# SCH_Amogus-Buzzer_2024-08-13.net
KiCad netlist of a schematic drawn in EasyEDA
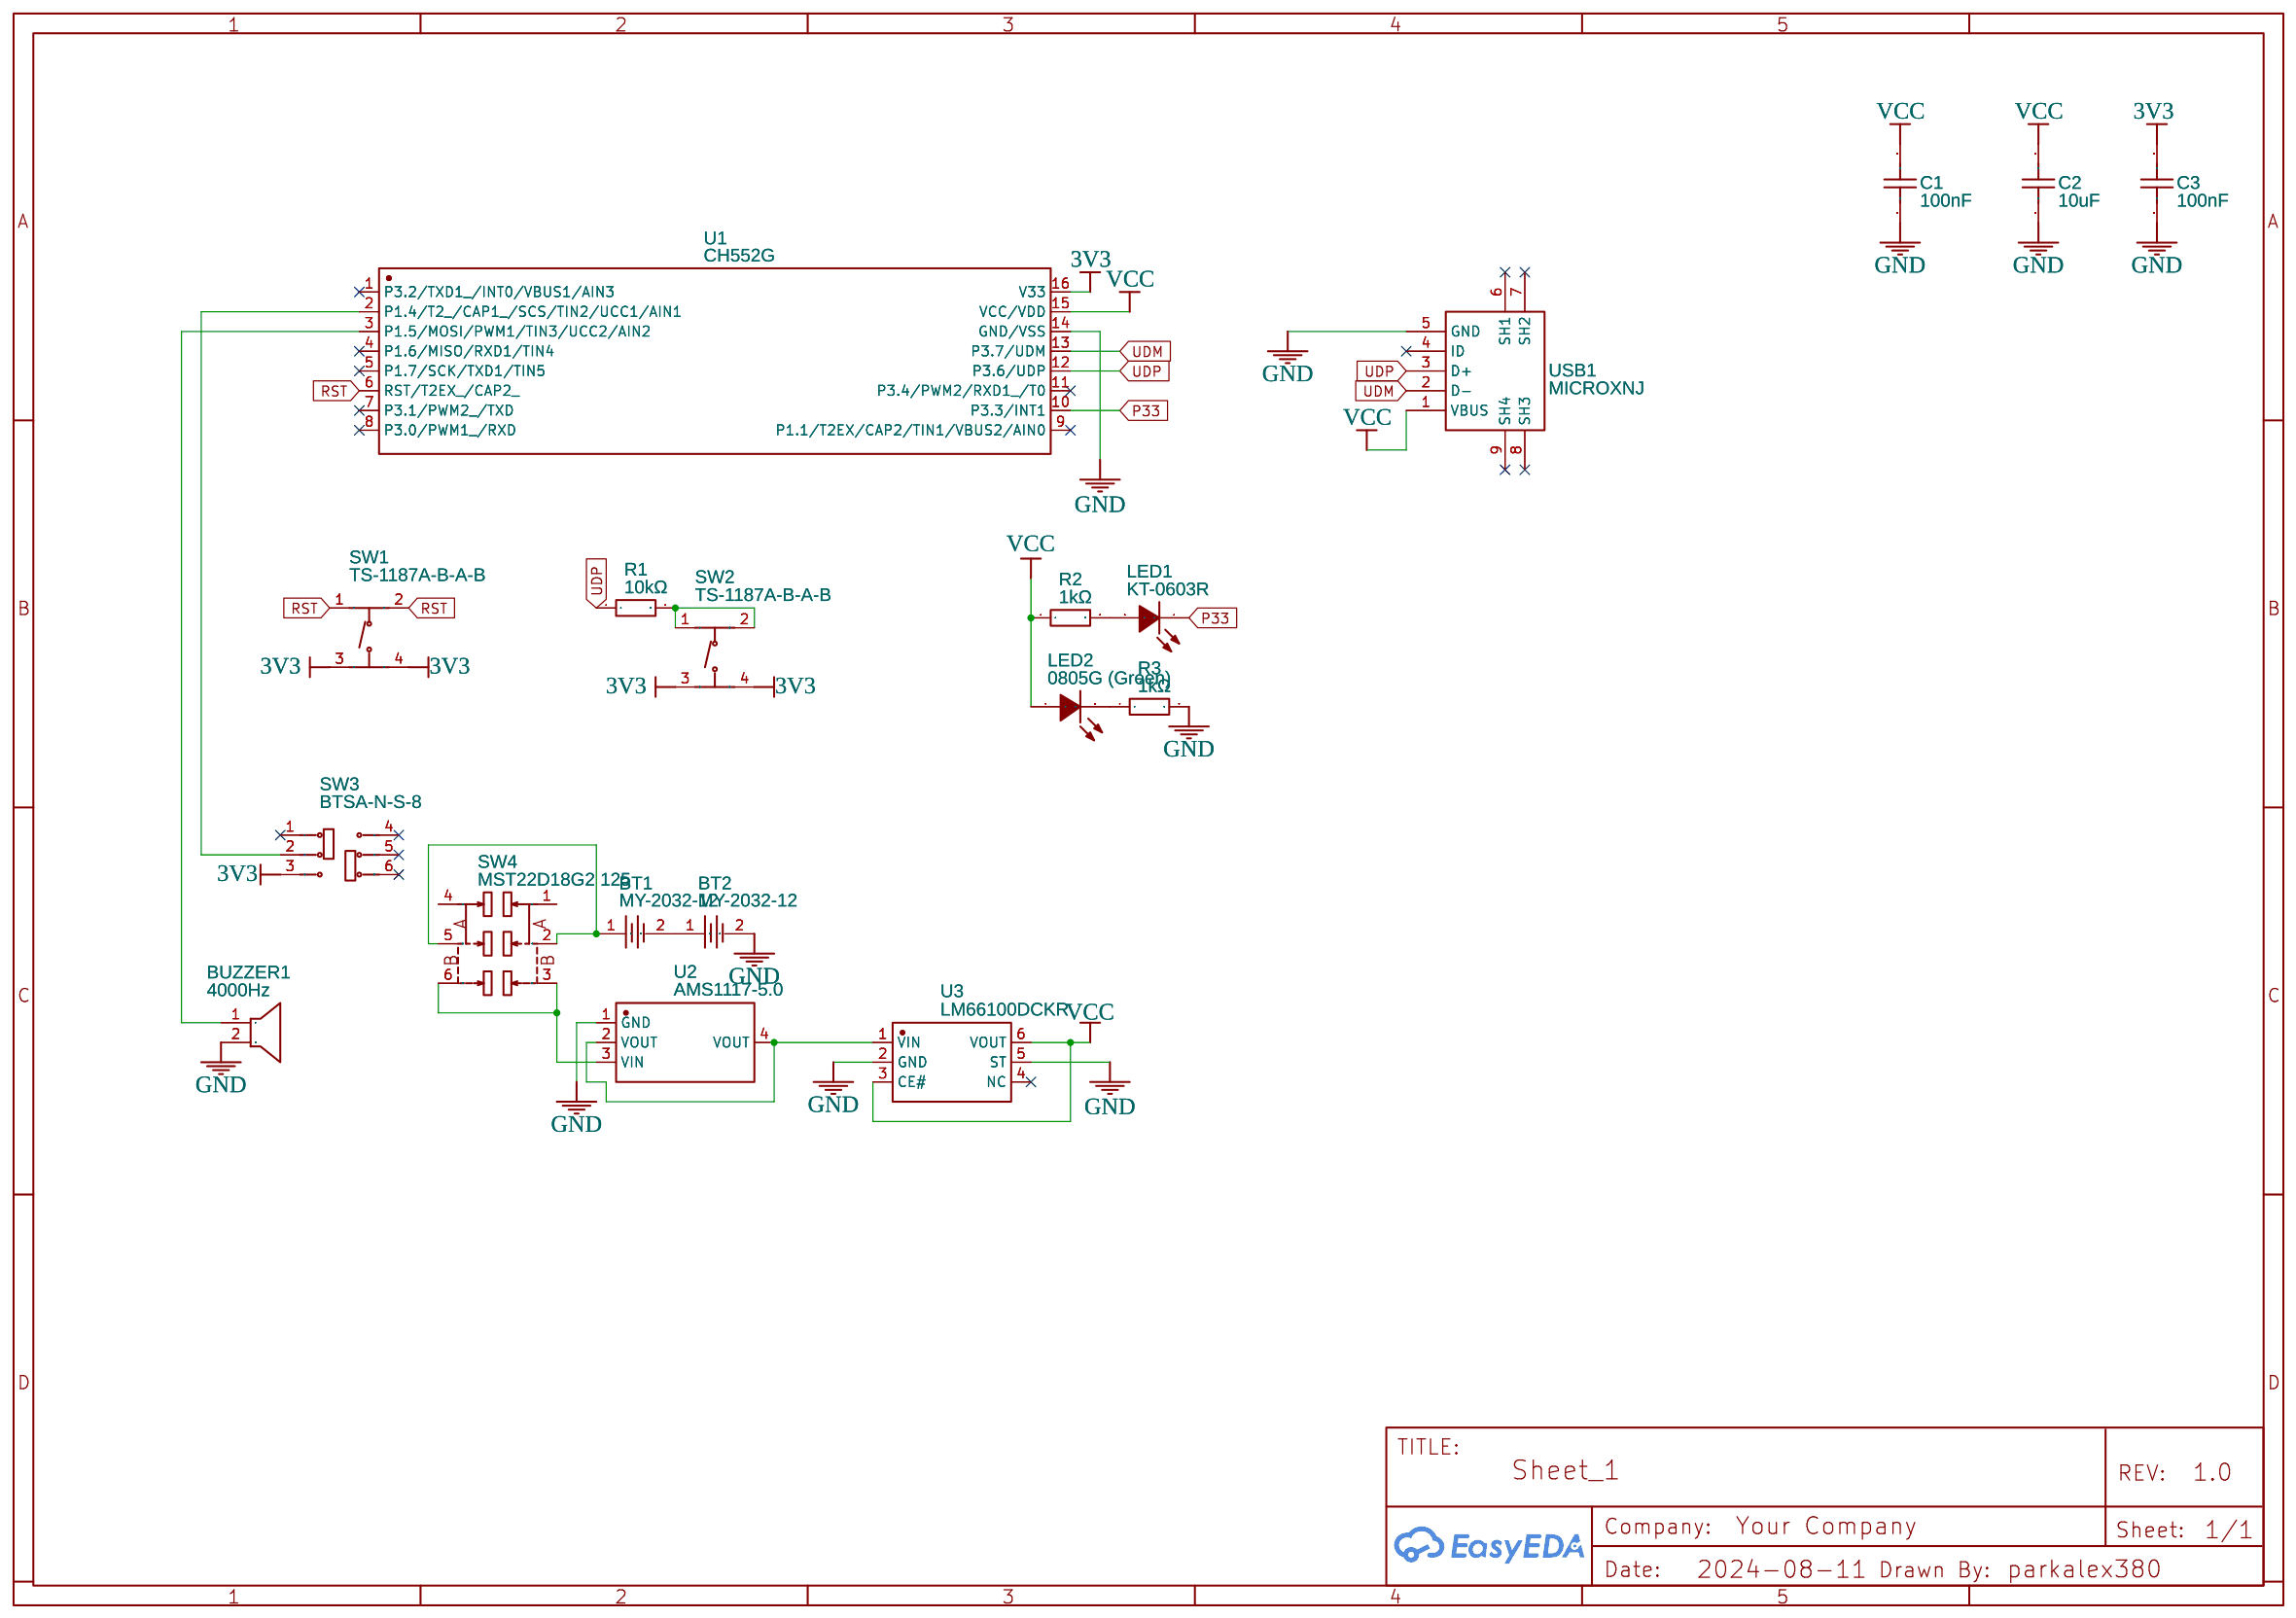
[diagram p0: schematic sheet]

(export (version "E")
  (design (tool "Eeschema 10.0.6"))
  (components
    (comp (ref "BT1")
      (value "MY-2032-12")
      (fields (field (name "Manufacturer") "MYOUNG(美阳)"))
      (libsource (lib "") (part "MY-2032-12"))
    )
    (comp (ref "BT2")
      (value "MY-2032-12")
      (fields (field (name "Manufacturer") "MYOUNG(美阳)"))
      (libsource (lib "") (part "MY-2032-12"))
    )
    (comp (ref "BUZZER1")
      (value "4000Hz")
      (fields (field (name "Manufacturer Part") "GPC12075YB-5V") (field (name "Manufacturer") "INGHAi(赢海)"))
      (libsource (lib "") (part "GPC12075YB-5V"))
    )
    (comp (ref "C1")
      (value "100nF")
      (fields
        (field (name "Manufacturer Part") "CC0603KRX7R9BB104")
        (field (name "Manufacturer") "YAGEO(国巨)")
      )
      (libsource (lib "") (part "CC0603KRX7R9BB104"))
    )
    (comp (ref "C2")
      (value "10uF")
      (fields
        (field (name "Manufacturer Part") "CL21A106KAYNNNE")
        (field (name "Manufacturer") "SAMSUNG(三星)")
      )
      (libsource (lib "") (part "CL21A106KAYNNNE"))
    )
    (comp (ref "C3")
      (value "100nF")
      (fields
        (field (name "Manufacturer Part") "CC0603KRX7R9BB104")
        (field (name "Manufacturer") "YAGEO(国巨)")
      )
      (libsource (lib "") (part "CC0603KRX7R9BB104"))
    )
    (comp (ref "LED1")
      (value "KT-0603R")
      (fields (field (name "Manufacturer") "KENTO"))
      (libsource (lib "") (part "KT-0603R"))
    )
    (comp (ref "LED2")
      (value "0805G (Green)")
      (fields (field (name "Manufacturer Part") "KT-0805G") (field (name "Manufacturer") "KENTO"))
      (libsource (lib "") (part "0805G (Green)"))
    )
    (comp (ref "R1")
      (value "10kΩ")
      (fields
        (field (name "Manufacturer Part") "0603WAF1002T5E")
        (field (name "Manufacturer") "UNI-ROYAL(厚声)")
      )
      (libsource (lib "") (part "0603WAF1002T5E"))
    )
    (comp (ref "R2")
      (value "1kΩ")
      (fields
        (field (name "Manufacturer Part") "0603WAF1001T5E")
        (field (name "Manufacturer") "UNI-ROYAL(厚声)")
      )
      (libsource (lib "") (part "0603WAF1001T5E"))
    )
    (comp (ref "R3")
      (value "1kΩ")
      (fields
        (field (name "Manufacturer Part") "0603WAF1001T5E")
        (field (name "Manufacturer") "UNI-ROYAL(厚声)")
      )
      (libsource (lib "") (part "0603WAF1001T5E"))
    )
    (comp (ref "SW1")
      (value "TS-1187A-B-A-B")
      (fields (field (name "Manufacturer") "XKB Connectivity(中国星坤)"))
      (libsource (lib "") (part "TS-1187A-B-A-B"))
    )
    (comp (ref "SW2")
      (value "TS-1187A-B-A-B")
      (fields (field (name "Manufacturer") "XKB Connectivity(中国星坤)"))
      (libsource (lib "") (part "TS-1187A-B-A-B"))
    )
    (comp (ref "SW3")
      (value "BTSA-N-S-8")
      (fields (field (name "Manufacturer") "ROCPU Switches(台普)"))
      (libsource (lib "") (part "BTSA-N-S-8"))
    )
    (comp (ref "SW4")
      (value "MST22D18G2 125")
      (fields (field (name "Manufacturer") "SHOU HAN(首韩)"))
      (libsource (lib "") (part "MST22D18G2 125"))
    )
    (comp (ref "U1")
      (value "CH552G")
      (fields (field (name "Manufacturer") "WCH(南京沁恒)"))
      (libsource (lib "") (part "CH552G"))
    )
    (comp (ref "U2")
      (value "AMS1117-5.0")
      (fields (field (name "Manufacturer") "AMS"))
      (libsource (lib "") (part "AMS1117-5.0"))
    )
    (comp (ref "U3")
      (value "LM66100DCKR")
      (fields (field (name "Manufacturer") "TI(德州仪器)"))
      (libsource (lib "") (part "LM66100DCKR"))
    )
    (comp (ref "USB1")
      (value "MICROXNJ")
      (fields (field (name "Manufacturer Part") "MicroXNJ") (field (name "Manufacturer") "SHOU HAN(首韩)"))
      (libsource (lib "") (part "MICROXNJ"))
    )
  )
  (nets
    (net (code "1") (name "3V3") (class "Default")
      (node (ref "C3") (pin "2") (pinfunction "2_2") (pintype "unspecified"))
      (node (ref "SW1") (pin "3") (pinfunction "C_3") (pintype "unspecified"))
      (node (ref "SW1") (pin "4") (pinfunction "D_4") (pintype "unspecified"))
      (node (ref "SW2") (pin "3") (pinfunction "C_3") (pintype "unspecified"))
      (node (ref "SW2") (pin "4") (pinfunction "D_4") (pintype "unspecified"))
      (node (ref "SW3") (pin "3") (pinfunction "3_3") (pintype "unspecified"))
      (node (ref "U1") (pin "16") (pinfunction "V33_16") (pintype "unspecified"))
    )
    (net (code "2") (name "GND") (class "Default")
      (node (ref "BT2") (pin "2") (pinfunction "2_2") (pintype "input"))
      (node (ref "BUZZER1") (pin "2") (pinfunction "2_2") (pintype "unspecified"))
      (node (ref "C1") (pin "1") (pinfunction "1_1") (pintype "unspecified"))
      (node (ref "C2") (pin "2") (pinfunction "2_2") (pintype "unspecified"))
      (node (ref "C3") (pin "1") (pinfunction "1_1") (pintype "unspecified"))
      (node (ref "R3") (pin "2") (pinfunction "2_2") (pintype "input"))
      (node (ref "U1") (pin "14") (pinfunction "GND/VSS_14") (pintype "unspecified"))
      (node (ref "U2") (pin "1") (pinfunction "GND_1") (pintype "unspecified"))
      (node (ref "U3") (pin "2") (pinfunction "GND_2") (pintype "unspecified"))
      (node (ref "U3") (pin "5") (pinfunction "ST_5") (pintype "unspecified"))
      (node (ref "USB1") (pin "5") (pinfunction "GND_5") (pintype "unspecified"))
    )
    (net (code "3") (name "Net-(BT1-Pad1)") (class "Default")
      (node (ref "BT1") (pin "1") (pinfunction "1_1") (pintype "input"))
      (node (ref "SW4") (pin "2") (pinfunction "2_2") (pintype "unspecified"))
      (node (ref "SW4") (pin "5") (pinfunction "5_5") (pintype "unspecified"))
    )
    (net (code "4") (name "Net-(BT1-Pad2)") (class "Default")
      (node (ref "BT1") (pin "2") (pinfunction "2_2") (pintype "input"))
      (node (ref "BT2") (pin "1") (pinfunction "1_1") (pintype "input"))
    )
    (net (code "5") (name "Net-(LED1-A)") (class "Default")
      (node (ref "LED1") (pin "2") (pinfunction "A_2") (pintype "unspecified"))
      (node (ref "R2") (pin "2") (pinfunction "2_2") (pintype "input"))
    )
    (net (code "6") (name "Net-(LED2-K)") (class "Default")
      (node (ref "LED2") (pin "2") (pinfunction "K_2") (pintype "unspecified"))
      (node (ref "R3") (pin "1") (pinfunction "1_1") (pintype "input"))
    )
    (net (code "7") (name "Net-(SW2-A)") (class "Default")
      (node (ref "R1") (pin "2") (pinfunction "2_2") (pintype "input"))
      (node (ref "SW2") (pin "1") (pinfunction "A_1") (pintype "unspecified"))
      (node (ref "SW2") (pin "2") (pinfunction "B_2") (pintype "unspecified"))
    )
    (net (code "8") (name "Net-(U1-P1.4{slash}T2_{slash}CAP1_{slash}SCS{slash}TIN2{slash}UCC1{slash}AIN1)") (class "Default")
      (node (ref "SW3") (pin "2") (pinfunction "2_2") (pintype "unspecified"))
      (node (ref "U1") (pin "2") (pinfunction "P1.4/T2_/CAP1_/SCS/TIN2/UCC1/AIN1_2") (pintype "unspecified"))
    )
    (net (code "9") (name "Net-(U1-P1.5{slash}MOSI{slash}PWM1{slash}TIN3{slash}UCC2{slash}AIN2)") (class "Default")
      (node (ref "BUZZER1") (pin "1") (pinfunction "1_1") (pintype "unspecified"))
      (node (ref "U1") (pin "3") (pinfunction "P1.5/MOSI/PWM1/TIN3/UCC2/AIN2_3") (pintype "unspecified"))
    )
    (net (code "10") (name "Net-(U2-VIN)") (class "Default")
      (node (ref "SW4") (pin "3") (pinfunction "3_3") (pintype "unspecified"))
      (node (ref "SW4") (pin "6") (pinfunction "6_6") (pintype "unspecified"))
      (node (ref "U2") (pin "3") (pinfunction "VIN_3") (pintype "unspecified"))
    )
    (net (code "11") (name "Net-(U3-VIN)") (class "Default")
      (node (ref "U2") (pin "2") (pinfunction "VOUT_2") (pintype "unspecified"))
      (node (ref "U2") (pin "4") (pinfunction "VOUT_4") (pintype "unspecified"))
      (node (ref "U3") (pin "1") (pinfunction "VIN_1") (pintype "unspecified"))
    )
    (net (code "12") (name "P33") (class "Default")
      (node (ref "LED1") (pin "1") (pinfunction "K_1") (pintype "unspecified"))
      (node (ref "U1") (pin "10") (pinfunction "P3.3/INT1_10") (pintype "unspecified"))
    )
    (net (code "13") (name "RST") (class "Default")
      (node (ref "SW1") (pin "1") (pinfunction "A_1") (pintype "unspecified"))
      (node (ref "SW1") (pin "2") (pinfunction "B_2") (pintype "unspecified"))
      (node (ref "U1") (pin "6") (pinfunction "RST/T2EX_/CAP2__6") (pintype "unspecified"))
    )
    (net (code "14") (name "UDM") (class "Default")
      (node (ref "U1") (pin "13") (pinfunction "P3.7/UDM_13") (pintype "unspecified"))
      (node (ref "USB1") (pin "2") (pinfunction "D-_2") (pintype "unspecified"))
    )
    (net (code "15") (name "UDP") (class "Default")
      (node (ref "R1") (pin "1") (pinfunction "1_1") (pintype "input"))
      (node (ref "U1") (pin "12") (pinfunction "P3.6/UDP_12") (pintype "unspecified"))
      (node (ref "USB1") (pin "3") (pinfunction "D+_3") (pintype "unspecified"))
    )
    (net (code "16") (name "VCC") (class "Default")
      (node (ref "C1") (pin "2") (pinfunction "2_2") (pintype "unspecified"))
      (node (ref "C2") (pin "1") (pinfunction "1_1") (pintype "unspecified"))
      (node (ref "LED2") (pin "1") (pinfunction "A_1") (pintype "unspecified"))
      (node (ref "R2") (pin "1") (pinfunction "1_1") (pintype "input"))
      (node (ref "U1") (pin "15") (pinfunction "VCC/VDD_15") (pintype "unspecified"))
      (node (ref "U3") (pin "3") (pinfunction "CE#_3") (pintype "unspecified"))
      (node (ref "U3") (pin "6") (pinfunction "VOUT_6") (pintype "unspecified"))
      (node (ref "USB1") (pin "1") (pinfunction "VBUS_1") (pintype "unspecified"))
    )
    (net (code "17") (name "unconnected-(SW3-Pad1)") (class "Default")
      (node (ref "SW3") (pin "1") (pinfunction "1_1") (pintype "unspecified+no_connect"))
    )
    (net (code "18") (name "unconnected-(SW3-Pad4)") (class "Default")
      (node (ref "SW3") (pin "4") (pinfunction "4_4") (pintype "unspecified+no_connect"))
    )
    (net (code "19") (name "unconnected-(SW3-Pad5)") (class "Default")
      (node (ref "SW3") (pin "5") (pinfunction "5_5") (pintype "unspecified+no_connect"))
    )
    (net (code "20") (name "unconnected-(SW3-Pad6)") (class "Default")
      (node (ref "SW3") (pin "6") (pinfunction "6_6") (pintype "unspecified+no_connect"))
    )
    (net (code "21") (name "unconnected-(SW4-Pad1)") (class "Default")
      (node (ref "SW4") (pin "1") (pinfunction "1_1") (pintype "unspecified"))
    )
    (net (code "22") (name "unconnected-(SW4-Pad4)") (class "Default")
      (node (ref "SW4") (pin "4") (pinfunction "4_4") (pintype "unspecified"))
    )
    (net (code "23") (name "unconnected-(U1-P1.1{slash}T2EX{slash}CAP2{slash}TIN1{slash}VBUS2{slash}AIN0-Pad9)") (class "Default")
      (node (ref "U1") (pin "9") (pinfunction "P1.1/T2EX/CAP2/TIN1/VBUS2/AIN0_9") (pintype "unspecified+no_connect"))
    )
    (net (code "24") (name "unconnected-(U1-P1.6{slash}MISO{slash}RXD1{slash}TIN4-Pad4)") (class "Default")
      (node (ref "U1") (pin "4") (pinfunction "P1.6/MISO/RXD1/TIN4_4") (pintype "unspecified+no_connect"))
    )
    (net (code "25") (name "unconnected-(U1-P1.7{slash}SCK{slash}TXD1{slash}TIN5-Pad5)") (class "Default")
      (node (ref "U1") (pin "5") (pinfunction "P1.7/SCK/TXD1/TIN5_5") (pintype "unspecified+no_connect"))
    )
    (net (code "26") (name "unconnected-(U1-P3.0{slash}PWM1_{slash}RXD-Pad8)") (class "Default")
      (node (ref "U1") (pin "8") (pinfunction "P3.0/PWM1_/RXD_8") (pintype "unspecified+no_connect"))
    )
    (net (code "27") (name "unconnected-(U1-P3.1{slash}PWM2_{slash}TXD-Pad7)") (class "Default")
      (node (ref "U1") (pin "7") (pinfunction "P3.1/PWM2_/TXD_7") (pintype "unspecified+no_connect"))
    )
    (net (code "28") (name "unconnected-(U1-P3.2{slash}TXD1_{slash}INT0{slash}VBUS1{slash}AIN3-Pad1)") (class "Default")
      (node (ref "U1") (pin "1") (pinfunction "P3.2/TXD1_/INT0/VBUS1/AIN3_1") (pintype "unspecified+no_connect"))
    )
    (net (code "29") (name "unconnected-(U1-P3.4{slash}PWM2{slash}RXD1_{slash}T0-Pad11)") (class "Default")
      (node (ref "U1") (pin "11") (pinfunction "P3.4/PWM2/RXD1_/T0_11") (pintype "unspecified+no_connect"))
    )
    (net (code "30") (name "unconnected-(U3-NC-Pad4)") (class "Default")
      (node (ref "U3") (pin "4") (pinfunction "NC_4") (pintype "unspecified+no_connect"))
    )
    (net (code "31") (name "unconnected-(USB1-ID-Pad4)") (class "Default")
      (node (ref "USB1") (pin "4") (pinfunction "ID_4") (pintype "unspecified+no_connect"))
    )
    (net (code "32") (name "unconnected-(USB1-SH1-Pad6)") (class "Default")
      (node (ref "USB1") (pin "6") (pinfunction "SH1_6") (pintype "unspecified+no_connect"))
    )
    (net (code "33") (name "unconnected-(USB1-SH2-Pad7)") (class "Default")
      (node (ref "USB1") (pin "7") (pinfunction "SH2_7") (pintype "unspecified+no_connect"))
    )
    (net (code "34") (name "unconnected-(USB1-SH3-Pad8)") (class "Default")
      (node (ref "USB1") (pin "8") (pinfunction "SH3_8") (pintype "unspecified+no_connect"))
    )
    (net (code "35") (name "unconnected-(USB1-SH4-Pad9)") (class "Default")
      (node (ref "USB1") (pin "9") (pinfunction "SH4_9") (pintype "unspecified+no_connect"))
    )
  )
)
